# 5_12VSupply.net
KiCad netlist of a schematic drawn in Altium Designer
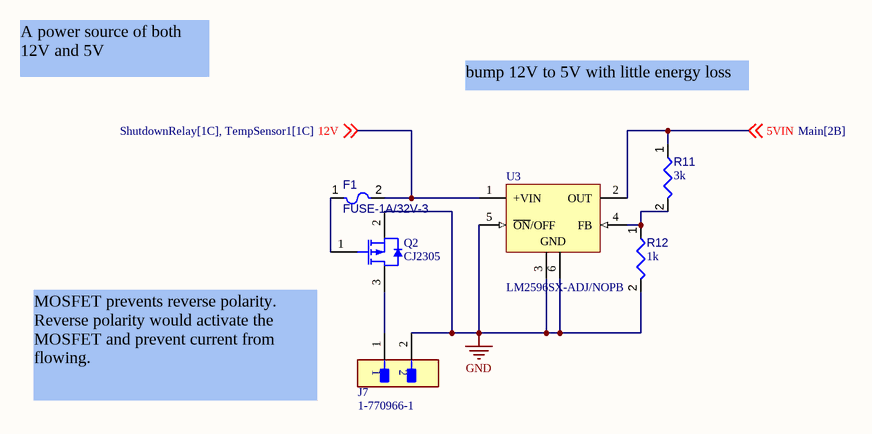
[diagram p0: 5,12VSupply.SchDoc]

(export (version "E")
  (design (tool "Eeschema 10.0.6"))
  (components
    (comp (ref "F1")
      (value "FUSE-1A/32V-3")
      (footprint "LFUS-467_V")
      (description "Fast Acting Fuse, 1 A, 32 V, -55 to 90 degC, 2-Pin SMD, RoHS, Tape and Reel")
      (libsource (lib "Alt_ium Course") (part "CMP-001-0019-1"))
    )
    (comp (ref "J7")
      (value "1-770966-1")
      (footprint "FP-1-770966-1-MFG")
      (description "CONN HEADER R/A 2POS 4.14MM")
      (fields
        (field (name "OCTOPART") "https://octopart.com/1-770966-1-te+connectivity-46506767")
        (field (name "MANUFACTURER") "TE")
      )
      (libsource (lib "Altium Content Vault") (part "3bc925449376181038e59eaffc5286c"))
    )
    (comp (ref "Q2")
      (value "CJ2305")
      (footprint "JSCJ-SOT23-3_V")
      (description "P-Channel Plastic Encapsulate MOSFET, 12 V, 4.1 A, 3-Pin SOT23, Tape and Reel")
      (fields (field (name "MANUFACTURER") "Jiangsu Changjiang Electronics Technology"))
      (libsource (lib "Alt_ium Course") (part "PEMOS-GSD-3"))
    )
    (comp (ref "R11")
      (value "3k")
      (footprint "RESC0402(1005)_L")
      (description "3K 0.063W 1% 0402 (1005 Metric)  SMD")
      (fields (field (name "POWER") "63mW") (field (name "TOLERANCE") "1%"))
      (libsource (lib "Alt_ium Course") (part "3KR2F"))
    )
    (comp (ref "R12")
      (value "1k")
      (footprint "RESC0402(1005)_L")
      (description "1K 0.063W 5% 0402 (1005 Metric)  SMD")
      (fields (field (name "POWER") "63mW") (field (name "TOLERANCE") "5%"))
      (libsource (lib "Alt_ium Course") (part "1KR2J"))
    )
    (comp (ref "U3")
      (value "LM2596SX-ADJ/NOPB")
      (footprint "KTT0005B_L")
      (fields (field (name "PARTNUMBER") "LM2596") (field (name "MANUFACTURER") "Texas Instruments"))
      (libsource (lib "Altium Content Vault") (part "TI-LM2596-TO-263-5"))
    )
  )
  (nets
    (net (code "1") (name "5VIN") (class "Default")
      (node (ref "R11") (pin "1") (pinfunction "1_1") (pintype "passive"))
      (node (ref "U3") (pin "2") (pinfunction "OUT_2") (pintype "power_in"))
    )
    (net (code "2") (name "12V") (class "Default")
      (node (ref "F1") (pin "2") (pinfunction "2_2") (pintype "passive"))
      (node (ref "U3") (pin "1") (pinfunction "+VIN_1") (pintype "power_in"))
    )
    (net (code "3") (name "GND") (class "Default")
      (node (ref "J7") (pin "2") (pinfunction "2_2") (pintype "passive"))
      (node (ref "Q2") (pin "2") (pinfunction "SOURCE_2") (pintype "passive"))
      (node (ref "R12") (pin "2") (pinfunction "2_2") (pintype "passive"))
      (node (ref "U3") (pin "3") (pinfunction "GND_3") (pintype "power_in"))
      (node (ref "U3") (pin "5") (pinfunction "~{ON}/OFF_5") (pintype "input"))
      (node (ref "U3") (pin "6") (pinfunction "GND_6") (pintype "power_in"))
    )
    (net (code "4") (name "Net-(Q2-DRAIN)") (class "Default")
      (node (ref "J7") (pin "1") (pinfunction "1_1") (pintype "passive"))
      (node (ref "Q2") (pin "3") (pinfunction "DRAIN_3") (pintype "passive"))
    )
    (net (code "5") (name "Net-(Q2-GATE)") (class "Default")
      (node (ref "F1") (pin "1") (pinfunction "1_1") (pintype "passive"))
      (node (ref "Q2") (pin "1") (pinfunction "GATE_1") (pintype "passive"))
    )
    (net (code "6") (name "Net-(U3-FB)") (class "Default")
      (node (ref "R11") (pin "2") (pinfunction "2_2") (pintype "passive"))
      (node (ref "R12") (pin "1") (pinfunction "1_1") (pintype "passive"))
      (node (ref "U3") (pin "4") (pinfunction "FB_4") (pintype "input"))
    )
  )
)
